# flowerfriend_rev3.net
KiCad netlist of a schematic drawn in EAGLE
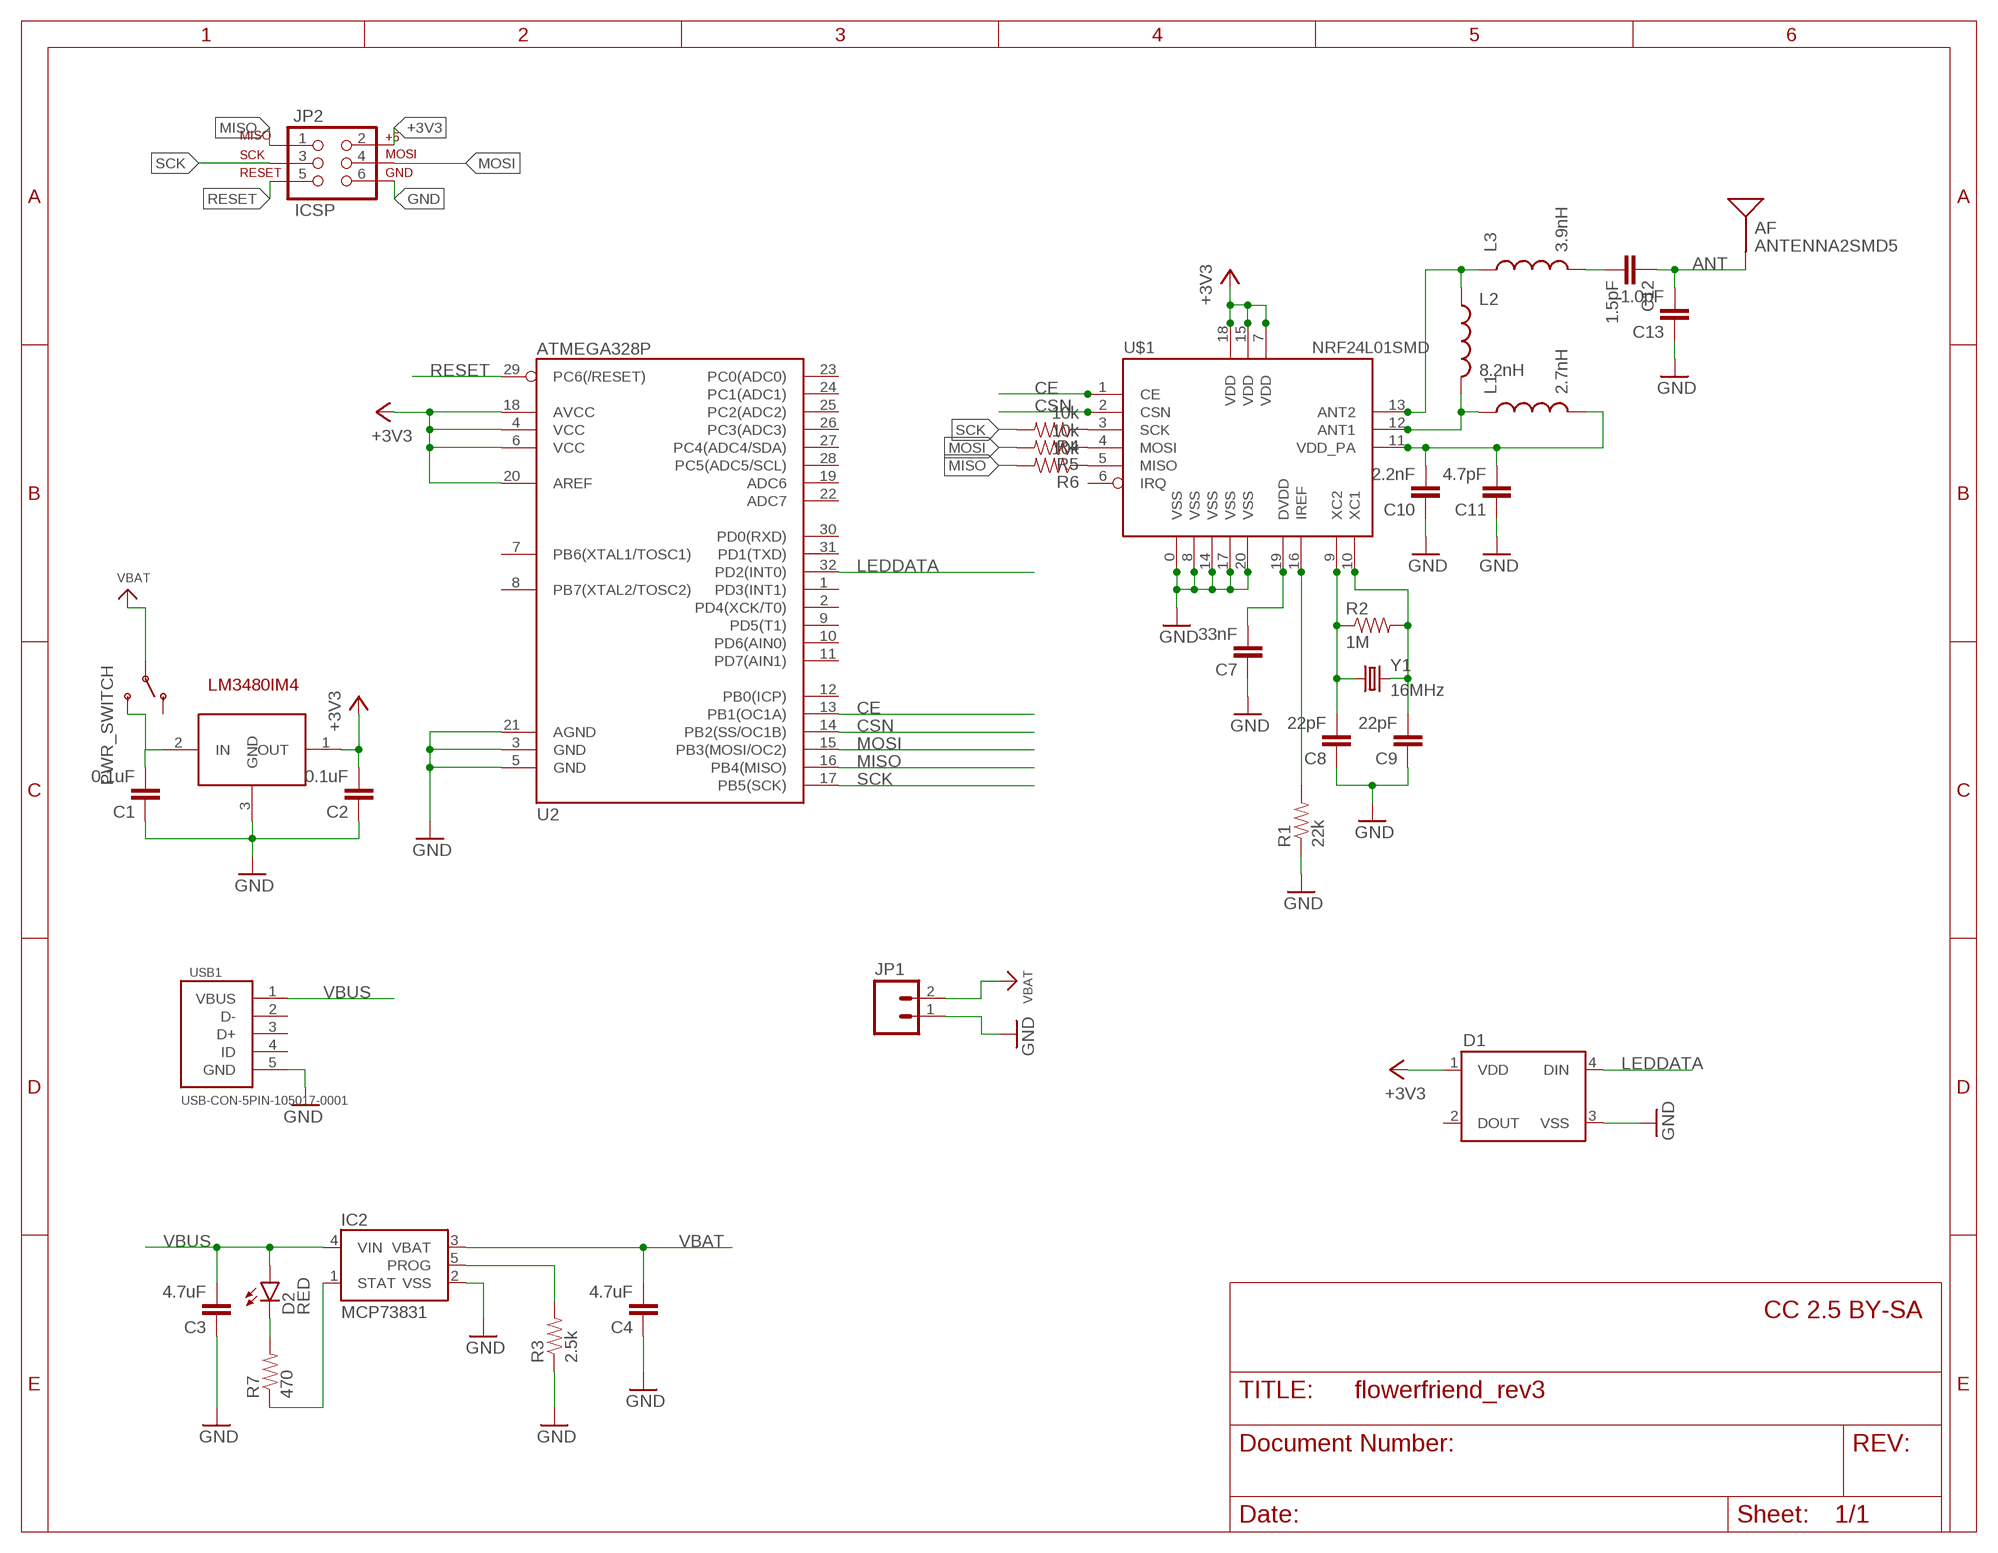
[diagram p0: schematic, sheet 1]

(export (version "E")
  (design (tool "Eeschema 10.0.6"))
  (components
    (comp (ref "AF")
      (value "ANTENNA2SMD5")
      (footprint "eagle-import:ANTENNA-CHIP5")
      (libsource (lib "eagle-import") (part "ANTENNA2SMD5"))
    )
    (comp (ref "C1")
      (value "0.1uF")
      (footprint "eagle-import:0805")
      (libsource (lib "eagle-import") (part "CAP0805"))
    )
    (comp (ref "C2")
      (value "0.1uF")
      (footprint "eagle-import:0805")
      (libsource (lib "eagle-import") (part "CAP0805"))
    )
    (comp (ref "C3")
      (value "4.7uF")
      (footprint "eagle-import:0805")
      (libsource (lib "eagle-import") (part "CAP0805"))
    )
    (comp (ref "C4")
      (value "4.7uF")
      (footprint "eagle-import:0805")
      (libsource (lib "eagle-import") (part "CAP0805"))
    )
    (comp (ref "C7")
      (value "33nF")
      (footprint "eagle-import:0805")
      (libsource (lib "eagle-import") (part "CAP0805"))
    )
    (comp (ref "C8")
      (value "22pF")
      (footprint "eagle-import:0805")
      (libsource (lib "eagle-import") (part "CAP0805"))
    )
    (comp (ref "C9")
      (value "22pF")
      (footprint "eagle-import:0805")
      (libsource (lib "eagle-import") (part "CAP0805"))
    )
    (comp (ref "C10")
      (value "2.2nF")
      (footprint "eagle-import:0805")
      (libsource (lib "eagle-import") (part "CAP0805"))
    )
    (comp (ref "C11")
      (value "4.7pF")
      (footprint "eagle-import:0805")
      (libsource (lib "eagle-import") (part "CAP0805"))
    )
    (comp (ref "C12")
      (value "1.5pF")
      (footprint "eagle-import:0805")
      (libsource (lib "eagle-import") (part "CAP0805"))
    )
    (comp (ref "C13")
      (value "1.0pF")
      (footprint "eagle-import:0805")
      (libsource (lib "eagle-import") (part "CAP0805"))
    )
    (comp (ref "D1")
      (value "WS2812B")
      (footprint "eagle-import:WS2812B")
      (libsource (lib "eagle-import") (part "WS2812B"))
    )
    (comp (ref "D2")
      (value "RED")
      (footprint "eagle-import:LED-0603")
      (libsource (lib "eagle-import") (part "LED-RED0603"))
    )
    (comp (ref "IC1")
      (value "LM3480IM4")
      (footprint "eagle-import:SOT23-3")
      (libsource (lib "eagle-import") (part "LM3480IM4"))
    )
    (comp (ref "IC2")
      (value "MCP73831")
      (footprint "eagle-import:SOT23-5")
      (libsource (lib "eagle-import") (part "MCP73831"))
    )
    (comp (ref "JP1")
      (value "M02PTH")
      (footprint "eagle-import:1X02")
      (libsource (lib "eagle-import") (part "M02PTH"))
    )
    (comp (ref "JP2")
      (value "ICSP")
      (footprint "eagle-import:2X3")
      (libsource (lib "eagle-import") (part "AVR_SPI_PRG_6PTH"))
    )
    (comp (ref "L1")
      (value "2.7nH")
      (footprint "eagle-import:0805")
      (libsource (lib "eagle-import") (part "INDUCTOR0805"))
    )
    (comp (ref "L2")
      (value "8.2nH")
      (footprint "eagle-import:0805")
      (libsource (lib "eagle-import") (part "INDUCTOR0805"))
    )
    (comp (ref "L3")
      (value "3.9nH")
      (footprint "eagle-import:0805")
      (libsource (lib "eagle-import") (part "INDUCTOR0805"))
    )
    (comp (ref "PWR_SWITCH")
      (value "SWITCH_SPDT")
      (footprint "eagle-import:KPS-1290")
      (libsource (lib "eagle-import") (part "SWITCH_SPDT"))
    )
    (comp (ref "R1")
      (value "22k")
      (footprint "eagle-import:0805")
      (libsource (lib "eagle-import") (part "RESISTOR0805-RES"))
    )
    (comp (ref "R2")
      (value "1M")
      (footprint "eagle-import:0805")
      (libsource (lib "eagle-import") (part "RESISTOR0805-RES"))
    )
    (comp (ref "R3")
      (value "2.5k")
      (footprint "eagle-import:0805")
      (libsource (lib "eagle-import") (part "RESISTOR0805-RES"))
    )
    (comp (ref "R4")
      (value "10k")
      (footprint "eagle-import:0805")
      (libsource (lib "eagle-import") (part "RESISTOR0805-RES"))
    )
    (comp (ref "R5")
      (value "10k")
      (footprint "eagle-import:0805")
      (libsource (lib "eagle-import") (part "RESISTOR0805-RES"))
    )
    (comp (ref "R6")
      (value "10k")
      (footprint "eagle-import:0805")
      (libsource (lib "eagle-import") (part "RESISTOR0805-RES"))
    )
    (comp (ref "R7")
      (value "470")
      (footprint "eagle-import:0805")
      (libsource (lib "eagle-import") (part "RESISTOR0805-RES"))
    )
    (comp (ref "U$1")
      (value "NRF24L01SMD")
      (footprint "eagle-import:QFN20")
      (libsource (lib "eagle-import") (part "NRF24L01SMD"))
    )
    (comp (ref "U2")
      (value "ATMEGA328P")
      (footprint "eagle-import:TQFP32-08")
      (libsource (lib "eagle-import") (part "ATMEGA328_SMT"))
    )
    (comp (ref "USB1")
      (value "USB-CON-5PIN-105017-0001")
      (footprint "eagle-import:USB-MICRO-MOLEX-105017-0001")
      (libsource (lib "eagle-import") (part "USB-CON-5PIN-105017-0001"))
    )
    (comp (ref "Y1")
      (value "16MHz")
      (footprint "eagle-import:CRYSTAL-SMD-5X3")
      (libsource (lib "eagle-import") (part "CRYSTAL5X3"))
    )
  )
  (nets
    (net (code "1") (name "+3V3") (class "Default")
      (node (ref "C2") (pin "2") (pinfunction "2_2") (pintype "passive"))
      (node (ref "D1") (pin "1") (pinfunction "VDD_1") (pintype "power_in"))
      (node (ref "IC1") (pin "1") (pinfunction "OUT_1") (pintype "bidirectional"))
      (node (ref "JP2") (pin "2") (pinfunction "2_2") (pintype "passive"))
      (node (ref "U$1") (pin "15") (pinfunction "VDD_15") (pintype "power_in"))
      (node (ref "U$1") (pin "18") (pinfunction "VDD_18") (pintype "power_in"))
      (node (ref "U$1") (pin "7") (pinfunction "VDD_7") (pintype "power_in"))
      (node (ref "U2") (pin "18") (pinfunction "AVCC_18") (pintype "bidirectional"))
      (node (ref "U2") (pin "20") (pinfunction "AREF_20") (pintype "bidirectional"))
      (node (ref "U2") (pin "4") (pinfunction "VCC_4") (pintype "bidirectional"))
      (node (ref "U2") (pin "6") (pinfunction "VCC_6") (pintype "bidirectional"))
    )
    (net (code "2") (name "/ANT") (class "Default")
      (node (ref "AF") (pin "FEED") (pinfunction "SIGNAL_FEED") (pintype "bidirectional"))
      (node (ref "C12") (pin "1") (pinfunction "1_1") (pintype "passive"))
      (node (ref "C13") (pin "2") (pinfunction "2_2") (pintype "passive"))
    )
    (net (code "3") (name "/CE") (class "Default")
      (node (ref "U$1") (pin "1") (pinfunction "CE_1") (pintype "input"))
      (node (ref "U2") (pin "13") (pinfunction "PB1(OC1A)_13") (pintype "bidirectional"))
    )
    (net (code "4") (name "/CSN") (class "Default")
      (node (ref "U$1") (pin "2") (pinfunction "CSN_2") (pintype "input"))
      (node (ref "U2") (pin "14") (pinfunction "PB2(SS/OC1B)_14") (pintype "bidirectional"))
    )
    (net (code "5") (name "/LEDDATA") (class "Default")
      (node (ref "D1") (pin "4") (pinfunction "DIN_4") (pintype "input"))
      (node (ref "U2") (pin "32") (pinfunction "PD2(INT0)_32") (pintype "bidirectional"))
    )
    (net (code "6") (name "/VBUS") (class "Default")
      (node (ref "C3") (pin "2") (pinfunction "2_2") (pintype "passive"))
      (node (ref "D2") (pin "A") (pinfunction "A_A") (pintype "passive"))
      (node (ref "IC2") (pin "4") (pinfunction "VIN_4") (pintype "power_in"))
      (node (ref "USB1") (pin "1") (pinfunction "VBUS_1") (pintype "power_in"))
    )
    (net (code "7") (name "GND") (class "Default")
      (node (ref "C1") (pin "1") (pinfunction "1_1") (pintype "passive"))
      (node (ref "C10") (pin "1") (pinfunction "1_1") (pintype "passive"))
      (node (ref "C11") (pin "1") (pinfunction "1_1") (pintype "passive"))
      (node (ref "C13") (pin "1") (pinfunction "1_1") (pintype "passive"))
      (node (ref "C2") (pin "1") (pinfunction "1_1") (pintype "passive"))
      (node (ref "C3") (pin "1") (pinfunction "1_1") (pintype "passive"))
      (node (ref "C4") (pin "1") (pinfunction "1_1") (pintype "passive"))
      (node (ref "C7") (pin "1") (pinfunction "1_1") (pintype "passive"))
      (node (ref "C8") (pin "1") (pinfunction "1_1") (pintype "passive"))
      (node (ref "C9") (pin "1") (pinfunction "1_1") (pintype "passive"))
      (node (ref "D1") (pin "3") (pinfunction "VSS_3") (pintype "power_in"))
      (node (ref "IC1") (pin "3") (pinfunction "GND_3") (pintype "bidirectional"))
      (node (ref "IC2") (pin "2") (pinfunction "VSS_2") (pintype "power_in"))
      (node (ref "JP1") (pin "1") (pinfunction "1_1") (pintype "passive"))
      (node (ref "JP2") (pin "6") (pinfunction "6_6") (pintype "passive"))
      (node (ref "R1") (pin "1") (pinfunction "1_1") (pintype "passive"))
      (node (ref "R3") (pin "1") (pinfunction "1_1") (pintype "passive"))
      (node (ref "U$1") (pin "0") (pinfunction "VSS_0") (pintype "power_in"))
      (node (ref "U$1") (pin "14") (pinfunction "VSS_14") (pintype "power_in"))
      (node (ref "U$1") (pin "17") (pinfunction "VSS_17") (pintype "power_in"))
      (node (ref "U$1") (pin "20") (pinfunction "VSS_20") (pintype "power_in"))
      (node (ref "U$1") (pin "8") (pinfunction "VSS_8") (pintype "power_in"))
      (node (ref "U2") (pin "21") (pinfunction "AGND_21") (pintype "bidirectional"))
      (node (ref "U2") (pin "3") (pinfunction "GND_3") (pintype "bidirectional"))
      (node (ref "U2") (pin "5") (pinfunction "GND_5") (pintype "bidirectional"))
      (node (ref "USB1") (pin "5") (pinfunction "GND_5") (pintype "power_in"))
    )
    (net (code "8") (name "MISO") (class "Default")
      (node (ref "JP2") (pin "1") (pinfunction "1_1") (pintype "passive"))
      (node (ref "R6") (pin "2") (pinfunction "2_2") (pintype "passive"))
      (node (ref "U2") (pin "16") (pinfunction "PB4(MISO)_16") (pintype "bidirectional"))
    )
    (net (code "9") (name "MOSI") (class "Default")
      (node (ref "JP2") (pin "4") (pinfunction "4_4") (pintype "passive"))
      (node (ref "R5") (pin "2") (pinfunction "2_2") (pintype "passive"))
      (node (ref "U2") (pin "15") (pinfunction "PB3(MOSI/OC2)_15") (pintype "bidirectional"))
    )
    (net (code "10") (name "Net-(C12-Pad2)") (class "Default")
      (node (ref "C12") (pin "2") (pinfunction "2_2") (pintype "passive"))
      (node (ref "L3") (pin "2") (pinfunction "2_2") (pintype "passive"))
    )
    (net (code "11") (name "Net-(D2-PadC)") (class "Default")
      (node (ref "D2") (pin "C") (pinfunction "C_C") (pintype "passive"))
      (node (ref "R7") (pin "2") (pinfunction "2_2") (pintype "passive"))
    )
    (net (code "12") (name "Net-(IC1-IN)") (class "Default")
      (node (ref "C1") (pin "2") (pinfunction "2_2") (pintype "passive"))
      (node (ref "IC1") (pin "2") (pinfunction "IN_2") (pintype "bidirectional"))
      (node (ref "PWR_SWITCH") (pin "S") (pinfunction "S_S") (pintype "passive"))
    )
    (net (code "13") (name "Net-(IC2-PROG)") (class "Default")
      (node (ref "IC2") (pin "5") (pinfunction "PROG_5") (pintype "input"))
      (node (ref "R3") (pin "2") (pinfunction "2_2") (pintype "passive"))
    )
    (net (code "14") (name "Net-(IC2-STAT)") (class "Default")
      (node (ref "IC2") (pin "1") (pinfunction "STAT_1") (pintype "output"))
      (node (ref "R7") (pin "1") (pinfunction "1_1") (pintype "passive"))
    )
    (net (code "15") (name "Net-(U$1-ANT1)") (class "Default")
      (node (ref "L1") (pin "1") (pinfunction "1_1") (pintype "passive"))
      (node (ref "L2") (pin "2") (pinfunction "2_2") (pintype "passive"))
      (node (ref "U$1") (pin "12") (pinfunction "ANT1_12") (pintype "output"))
    )
    (net (code "16") (name "Net-(U$1-ANT2)") (class "Default")
      (node (ref "L2") (pin "1") (pinfunction "1_1") (pintype "passive"))
      (node (ref "L3") (pin "1") (pinfunction "1_1") (pintype "passive"))
      (node (ref "U$1") (pin "13") (pinfunction "ANT2_13") (pintype "output"))
    )
    (net (code "17") (name "Net-(U$1-DVDD)") (class "Default")
      (node (ref "C7") (pin "2") (pinfunction "2_2") (pintype "passive"))
      (node (ref "U$1") (pin "19") (pinfunction "DVDD_19") (pintype "power_in"))
    )
    (net (code "18") (name "Net-(U$1-IREF)") (class "Default")
      (node (ref "R1") (pin "2") (pinfunction "2_2") (pintype "passive"))
      (node (ref "U$1") (pin "16") (pinfunction "IREF_16") (pintype "input"))
    )
    (net (code "19") (name "Net-(U$1-MISO)") (class "Default")
      (node (ref "R6") (pin "1") (pinfunction "1_1") (pintype "passive"))
      (node (ref "U$1") (pin "5") (pinfunction "MISO_5") (pintype "output"))
    )
    (net (code "20") (name "Net-(U$1-MOSI)") (class "Default")
      (node (ref "R5") (pin "1") (pinfunction "1_1") (pintype "passive"))
      (node (ref "U$1") (pin "4") (pinfunction "MOSI_4") (pintype "input"))
    )
    (net (code "21") (name "Net-(U$1-SCK)") (class "Default")
      (node (ref "R4") (pin "1") (pinfunction "1_1") (pintype "passive"))
      (node (ref "U$1") (pin "3") (pinfunction "SCK_3") (pintype "input"))
    )
    (net (code "22") (name "Net-(U$1-VDD_PA)") (class "Default")
      (node (ref "C10") (pin "2") (pinfunction "2_2") (pintype "passive"))
      (node (ref "C11") (pin "2") (pinfunction "2_2") (pintype "passive"))
      (node (ref "L1") (pin "2") (pinfunction "2_2") (pintype "passive"))
      (node (ref "U$1") (pin "11") (pinfunction "VDD_PA_11") (pintype "power_in"))
    )
    (net (code "23") (name "Net-(U$1-XC1)") (class "Default")
      (node (ref "C9") (pin "2") (pinfunction "2_2") (pintype "passive"))
      (node (ref "R2") (pin "2") (pinfunction "2_2") (pintype "passive"))
      (node (ref "U$1") (pin "10") (pinfunction "XC1_10") (pintype "input"))
      (node (ref "Y1") (pin "3") (pinfunction "2_3") (pintype "passive"))
    )
    (net (code "24") (name "Net-(U$1-XC2)") (class "Default")
      (node (ref "C8") (pin "2") (pinfunction "2_2") (pintype "passive"))
      (node (ref "R2") (pin "1") (pinfunction "1_1") (pintype "passive"))
      (node (ref "U$1") (pin "9") (pinfunction "XC2_9") (pintype "input"))
      (node (ref "Y1") (pin "1") (pinfunction "1_1") (pintype "passive"))
    )
    (net (code "25") (name "RESET") (class "Default")
      (node (ref "JP2") (pin "5") (pinfunction "5_5") (pintype "passive"))
      (node (ref "U2") (pin "29") (pinfunction "PC6(/RESET)_29") (pintype "bidirectional"))
    )
    (net (code "26") (name "SCK") (class "Default")
      (node (ref "JP2") (pin "3") (pinfunction "3_3") (pintype "passive"))
      (node (ref "R4") (pin "2") (pinfunction "2_2") (pintype "passive"))
      (node (ref "U2") (pin "17") (pinfunction "PB5(SCK)_17") (pintype "bidirectional"))
    )
    (net (code "27") (name "VBAT") (class "Default")
      (node (ref "C4") (pin "2") (pinfunction "2_2") (pintype "passive"))
      (node (ref "IC2") (pin "3") (pinfunction "VBAT_3") (pintype "power_in"))
      (node (ref "JP1") (pin "2") (pinfunction "2_2") (pintype "passive"))
      (node (ref "PWR_SWITCH") (pin "P") (pinfunction "P_P") (pintype "passive"))
    )
    (net (code "28") (name "unconnected-(D1-DOUT-Pad2)") (class "Default")
      (node (ref "D1") (pin "2") (pinfunction "DOUT_2") (pintype "output"))
    )
    (net (code "29") (name "unconnected-(PWR_SWITCH-PadO)") (class "Default")
      (node (ref "PWR_SWITCH") (pin "O") (pinfunction "O_O") (pintype "passive"))
    )
    (net (code "30") (name "unconnected-(U$1-IRQ-Pad6)") (class "Default")
      (node (ref "U$1") (pin "6") (pinfunction "IRQ_6") (pintype "output"))
    )
    (net (code "31") (name "unconnected-(U2-ADC6-Pad19)") (class "Default")
      (node (ref "U2") (pin "19") (pinfunction "ADC6_19") (pintype "bidirectional"))
    )
    (net (code "32") (name "unconnected-(U2-ADC7-Pad22)") (class "Default")
      (node (ref "U2") (pin "22") (pinfunction "ADC7_22") (pintype "bidirectional"))
    )
    (net (code "33") (name "unconnected-(U2-PB0(ICP)-Pad12)") (class "Default")
      (node (ref "U2") (pin "12") (pinfunction "PB0(ICP)_12") (pintype "bidirectional"))
    )
    (net (code "34") (name "unconnected-(U2-PB6(XTAL1{slash}TOSC1)-Pad7)") (class "Default")
      (node (ref "U2") (pin "7") (pinfunction "PB6(XTAL1/TOSC1)_7") (pintype "bidirectional"))
    )
    (net (code "35") (name "unconnected-(U2-PB7(XTAL2{slash}TOSC2)-Pad8)") (class "Default")
      (node (ref "U2") (pin "8") (pinfunction "PB7(XTAL2/TOSC2)_8") (pintype "bidirectional"))
    )
    (net (code "36") (name "unconnected-(U2-PC0(ADC0)-Pad23)") (class "Default")
      (node (ref "U2") (pin "23") (pinfunction "PC0(ADC0)_23") (pintype "bidirectional"))
    )
    (net (code "37") (name "unconnected-(U2-PC1(ADC1)-Pad24)") (class "Default")
      (node (ref "U2") (pin "24") (pinfunction "PC1(ADC1)_24") (pintype "bidirectional"))
    )
    (net (code "38") (name "unconnected-(U2-PC2(ADC2)-Pad25)") (class "Default")
      (node (ref "U2") (pin "25") (pinfunction "PC2(ADC2)_25") (pintype "bidirectional"))
    )
    (net (code "39") (name "unconnected-(U2-PC3(ADC3)-Pad26)") (class "Default")
      (node (ref "U2") (pin "26") (pinfunction "PC3(ADC3)_26") (pintype "bidirectional"))
    )
    (net (code "40") (name "unconnected-(U2-PC4(ADC4{slash}SDA)-Pad27)") (class "Default")
      (node (ref "U2") (pin "27") (pinfunction "PC4(ADC4/SDA)_27") (pintype "bidirectional"))
    )
    (net (code "41") (name "unconnected-(U2-PC5(ADC5{slash}SCL)-Pad28)") (class "Default")
      (node (ref "U2") (pin "28") (pinfunction "PC5(ADC5/SCL)_28") (pintype "bidirectional"))
    )
    (net (code "42") (name "unconnected-(U2-PD0(RXD)-Pad30)") (class "Default")
      (node (ref "U2") (pin "30") (pinfunction "PD0(RXD)_30") (pintype "bidirectional"))
    )
    (net (code "43") (name "unconnected-(U2-PD1(TXD)-Pad31)") (class "Default")
      (node (ref "U2") (pin "31") (pinfunction "PD1(TXD)_31") (pintype "bidirectional"))
    )
    (net (code "44") (name "unconnected-(U2-PD3(INT1)-Pad1)") (class "Default")
      (node (ref "U2") (pin "1") (pinfunction "PD3(INT1)_1") (pintype "bidirectional"))
    )
    (net (code "45") (name "unconnected-(U2-PD4(XCK{slash}T0)-Pad2)") (class "Default")
      (node (ref "U2") (pin "2") (pinfunction "PD4(XCK/T0)_2") (pintype "bidirectional"))
    )
    (net (code "46") (name "unconnected-(U2-PD5(T1)-Pad9)") (class "Default")
      (node (ref "U2") (pin "9") (pinfunction "PD5(T1)_9") (pintype "bidirectional"))
    )
    (net (code "47") (name "unconnected-(U2-PD6(AIN0)-Pad10)") (class "Default")
      (node (ref "U2") (pin "10") (pinfunction "PD6(AIN0)_10") (pintype "bidirectional"))
    )
    (net (code "48") (name "unconnected-(U2-PD7(AIN1)-Pad11)") (class "Default")
      (node (ref "U2") (pin "11") (pinfunction "PD7(AIN1)_11") (pintype "bidirectional"))
    )
    (net (code "49") (name "unconnected-(USB1-D+-Pad3)") (class "Default")
      (node (ref "USB1") (pin "3") (pinfunction "D+_3") (pintype "bidirectional"))
    )
    (net (code "50") (name "unconnected-(USB1-D--Pad2)") (class "Default")
      (node (ref "USB1") (pin "2") (pinfunction "D-_2") (pintype "bidirectional"))
    )
    (net (code "51") (name "unconnected-(USB1-ID-Pad4)") (class "Default")
      (node (ref "USB1") (pin "4") (pinfunction "ID_4") (pintype "bidirectional"))
    )
  )
)
